# Output_Stages.net
KiCad netlist of a schematic drawn in Altium Designer
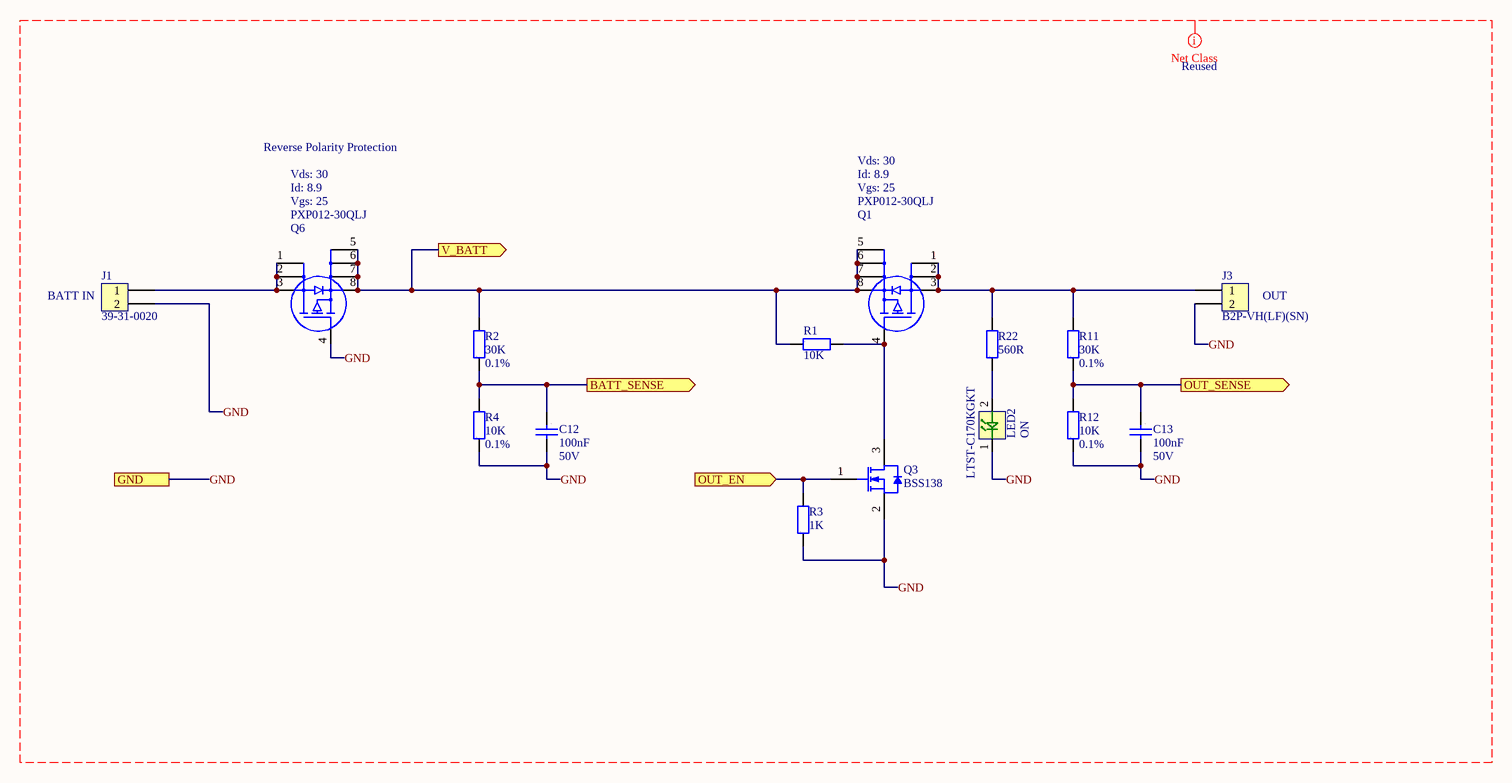
[diagram p0: Output Stages.SchDoc]

(export (version "E")
  (design (tool "Eeschema 10.0.6"))
  (components
    (comp (ref "C12")
      (value "100nF")
      (footprint "CAPC1608X08L")
      (description "Capacitor MLC 100nF 50V X7R 10% CAPC1608X08M")
      (fields
        (field (name "VOLTAGE") "50V")
        (field (name "MANUFACTURER") "Murata")
        (field (name "MANUPARTNO") "GRM188R71H104KA93D")
      )
      (libsource (lib "Library") (part "CAP"))
    )
    (comp (ref "C13")
      (value "100nF")
      (footprint "CAPC1608X08L")
      (description "Capacitor MLC 100nF 50V X7R 10% CAPC1608X08M")
      (fields
        (field (name "VOLTAGE") "50V")
        (field (name "MANUFACTURER") "Murata")
        (field (name "MANUPARTNO") "GRM188R71H104KA93D")
      )
      (libsource (lib "Library") (part "CAP"))
    )
    (comp (ref "J1")
      (value "BATT IN")
      (footprint "39-31-0020")
      (description "Connector 2 Way Mini-Fit 5566 Series")
      (fields (field (name "MANUPARTNO") "39-31-0020") (field (name "MANUFACTURER") "Molex"))
      (libsource (lib "") (part "CON2_1"))
    )
    (comp (ref "J3")
      (value "OUT")
      (footprint "B2P-VH")
      (description "Connector 2 Way Vertical JST B2P-VH(LF)(SN) 3.96mm Pitch")
      (fields (field (name "MANUPARTNO") "B2P-VH(LF)(SN)") (field (name "MANUFACTURER") "JST"))
      (libsource (lib "Library") (part "CON2"))
    )
    (comp (ref "LED2")
      (value "ON")
      (footprint "CAPCP2012X11N")
      (description "LED 2.0x1.25mm GREEN 0805 LTST-C170KGKT")
      (fields (field (name "MANUPARTNO") "LTST-C170KGKT") (field (name "MANUFACTURER") "Liteon"))
      (libsource (lib "Library") (part "LED_GREEN"))
    )
    (comp (ref "Q1")
      (value "*")
      (footprint "MLPAK33_SOT8002-1_NEX-M")
      (description "Power MOSFET, P Channel, 30 V, 15.2 A, 0.0111 ohm, MLPAK33, Surface Mount")
      (fields
        (field (name "MANUPARTNO") "PXP012-30QLJ")
        (field (name "VDS") "30")
        (field (name "ID") "8.9")
        (field (name "VGS") "25")
        (field (name "MANUFACTURER") "NEXPERIA")
      )
      (libsource (lib "") (part "FET_P_8_1"))
    )
    (comp (ref "Q3")
      (value "BSS138")
      (footprint "FAIR-SOT23-3_V")
      (fields (field (name "MANUFACTURER") "Fairchild") (field (name "POWER") "360mW"))
      (libsource (lib "Op Support Ltd") (part "NEMOS-GSD-3"))
    )
    (comp (ref "Q6")
      (value "Reverse Polarity Protection")
      (footprint "MLPAK33_SOT8002-1_NEX-M")
      (description "Power MOSFET, P Channel, 30 V, 15.2 A, 0.0111 ohm, MLPAK33, Surface Mount")
      (fields
        (field (name "MANUPARTNO") "PXP012-30QLJ")
        (field (name "VDS") "30")
        (field (name "ID") "8.9")
        (field (name "VGS") "25")
        (field (name "MANUFACTURER") "NEXPERIA")
      )
      (libsource (lib "Library") (part "FET_P_8"))
    )
    (comp (ref "R1")
      (value "10K")
      (footprint "RESC1608X06L")
      (description "SMD Chip Resistor, Thin Film, 10 kohm, 75 V, 0603 [1608 Metric], 100 mW, ± 0.1%, ERA3A Series")
      (fields (field (name "VOLTAGE") "75V") (field (name "MANUFACTURER") "Panasonic"))
      (libsource (lib "") (part "RESISTOR_1"))
    )
    (comp (ref "R2")
      (value "30K")
      (footprint "RESC1608X06L")
      (description "SMD Chip Resistor, Thin Film, 30 kohm, 75 V, 0603 [1608 Metric], 100 mW, ± 0.1%, ERA3A Series")
      (fields (field (name "TOLERANCE") "0.1%") (field (name "VOLTAGE") "75V") (field (name "POWER") "100mW"))
      (libsource (lib "Library") (part "RESISTOR"))
    )
    (comp (ref "R3")
      (value "1K")
      (footprint "RESC1608X06L")
      (description "SMD Chip Resistor, Thick Film, 1 kohm, 50 V, 0603 [1608 Metric], 100 mW, ± 1%, RC Series")
      (fields (field (name "VOLTAGE") "50V") (field (name "MANUFACTURER") "Yageo"))
      (libsource (lib "Library") (part "RESISTOR"))
    )
    (comp (ref "R4")
      (value "10K")
      (footprint "RESC1608X06L")
      (description "SMD Chip Resistor, Thin Film, 10 kohm, 75 V, 0603 [1608 Metric], 100 mW, ± 0.1%, ERA3A Series")
      (fields (field (name "TOLERANCE") "0.1%") (field (name "VOLTAGE") "75V") (field (name "POWER") "100mW"))
      (libsource (lib "Library") (part "RESISTOR"))
    )
    (comp (ref "R11")
      (value "30K")
      (footprint "RESC1608X06L")
      (description "SMD Chip Resistor, Thin Film, 30 kohm, 75 V, 0603 [1608 Metric], 100 mW, ± 0.1%, ERA3A Series")
      (fields (field (name "TOLERANCE") "0.1%") (field (name "VOLTAGE") "75V") (field (name "POWER") "100mW"))
      (libsource (lib "Library") (part "RESISTOR"))
    )
    (comp (ref "R12")
      (value "10K")
      (footprint "RESC1608X06L")
      (description "SMD Chip Resistor, Thin Film, 10 kohm, 75 V, 0603 [1608 Metric], 100 mW, ± 0.1%, ERA3A Series")
      (fields (field (name "TOLERANCE") "0.1%") (field (name "VOLTAGE") "75V") (field (name "POWER") "100mW"))
      (libsource (lib "Library") (part "RESISTOR"))
    )
    (comp (ref "R22")
      (value "560R")
      (footprint "RESC1608X06L")
      (description "Resistor 560R 1% 50V RESC1608X06M")
      (fields (field (name "VOLTAGE") "50V") (field (name "MANUFACTURER") "Multicomp"))
      (libsource (lib "Library") (part "RESISTOR"))
    )
  )
  (nets
    (net (code "1") (name "/BATT_SENSE") (class "Default")
      (node (ref "C12") (pin "1") (pinfunction "1_1") (pintype "passive"))
      (node (ref "R2") (pin "1") (pinfunction "1_1") (pintype "passive"))
      (node (ref "R4") (pin "2") (pinfunction "2_2") (pintype "passive"))
    )
    (net (code "2") (name "/GND") (class "Default")
      (node (ref "C12") (pin "2") (pinfunction "2_2") (pintype "passive"))
      (node (ref "C13") (pin "2") (pinfunction "2_2") (pintype "passive"))
      (node (ref "J1") (pin "2") (pinfunction "2_2") (pintype "passive"))
      (node (ref "J3") (pin "2") (pinfunction "2_2") (pintype "passive"))
      (node (ref "LED2") (pin "1") (pinfunction "1_1") (pintype "passive"))
      (node (ref "Q3") (pin "2") (pinfunction "S_2") (pintype "passive"))
      (node (ref "Q6") (pin "4") (pinfunction "Gate_4") (pintype "passive"))
      (node (ref "R12") (pin "1") (pinfunction "1_1") (pintype "passive"))
      (node (ref "R3") (pin "1") (pinfunction "1_1") (pintype "passive"))
      (node (ref "R4") (pin "1") (pinfunction "1_1") (pintype "passive"))
    )
    (net (code "3") (name "/OUT_EN") (class "Default")
      (node (ref "Q3") (pin "1") (pinfunction "G_1") (pintype "passive"))
      (node (ref "R3") (pin "2") (pinfunction "2_2") (pintype "passive"))
    )
    (net (code "4") (name "/OUT_SENSE") (class "Default")
      (node (ref "C13") (pin "1") (pinfunction "1_1") (pintype "passive"))
      (node (ref "R11") (pin "1") (pinfunction "1_1") (pintype "passive"))
      (node (ref "R12") (pin "2") (pinfunction "2_2") (pintype "passive"))
    )
    (net (code "5") (name "/V_BATT") (class "Default")
      (node (ref "Q1") (pin "5") (pinfunction "Source_5") (pintype "passive"))
      (node (ref "Q1") (pin "6") (pinfunction "Source_6") (pintype "passive"))
      (node (ref "Q1") (pin "7") (pinfunction "Source_7") (pintype "passive"))
      (node (ref "Q1") (pin "8") (pinfunction "Source_8") (pintype "passive"))
      (node (ref "Q6") (pin "5") (pinfunction "Source_5") (pintype "passive"))
      (node (ref "Q6") (pin "6") (pinfunction "Source_6") (pintype "passive"))
      (node (ref "Q6") (pin "7") (pinfunction "Source_7") (pintype "passive"))
      (node (ref "Q6") (pin "8") (pinfunction "Source_8") (pintype "passive"))
      (node (ref "R1") (pin "1") (pinfunction "1_1") (pintype "passive"))
      (node (ref "R2") (pin "2") (pinfunction "2_2") (pintype "passive"))
    )
    (net (code "6") (name "Net-(J1-Pad1)") (class "Default")
      (node (ref "J1") (pin "1") (pinfunction "1_1") (pintype "passive"))
      (node (ref "Q6") (pin "1") (pinfunction "Drain_1") (pintype "passive"))
      (node (ref "Q6") (pin "2") (pinfunction "Drain_2") (pintype "passive"))
      (node (ref "Q6") (pin "3") (pinfunction "Drain_3") (pintype "passive"))
    )
    (net (code "7") (name "Net-(J3-Pad1)") (class "Default")
      (node (ref "J3") (pin "1") (pinfunction "1_1") (pintype "passive"))
      (node (ref "Q1") (pin "1") (pinfunction "Drain_1") (pintype "passive"))
      (node (ref "Q1") (pin "2") (pinfunction "Drain_2") (pintype "passive"))
      (node (ref "Q1") (pin "3") (pinfunction "Drain_3") (pintype "passive"))
      (node (ref "R11") (pin "2") (pinfunction "2_2") (pintype "passive"))
      (node (ref "R22") (pin "2") (pinfunction "2_2") (pintype "passive"))
    )
    (net (code "8") (name "Net-(LED2-Pad2)") (class "Default")
      (node (ref "LED2") (pin "2") (pinfunction "2_2") (pintype "passive"))
      (node (ref "R22") (pin "1") (pinfunction "1_1") (pintype "passive"))
    )
    (net (code "9") (name "Net-(Q1-Gate)") (class "Default")
      (node (ref "Q1") (pin "4") (pinfunction "Gate_4") (pintype "passive"))
      (node (ref "Q3") (pin "3") (pinfunction "D_3") (pintype "passive"))
      (node (ref "R1") (pin "2") (pinfunction "2_2") (pintype "passive"))
    )
  )
)
